# adcUart.net
KiCad netlist of a schematic drawn in EAGLE
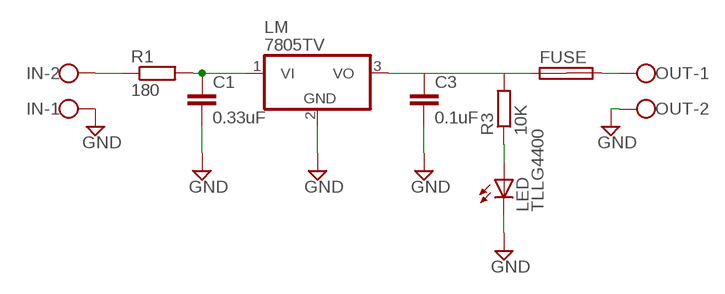
[diagram p0: schematic, sheet 1]

(export (version "E")
  (design (tool "Eeschema 10.0.6"))
  (components
    (comp (ref "C1")
      (value "0.33uF")
      (footprint "eagle-import:C025-024X044")
      (libsource (lib "eagle-import") (part "C-EU025-024X044"))
    )
    (comp (ref "C3")
      (value "0.1uF")
      (footprint "eagle-import:C025-024X044")
      (libsource (lib "eagle-import") (part "C-EU025-024X044"))
    )
    (comp (ref "FUSE")
      (value "SHK20L")
      (footprint "eagle-import:SHK20L")
      (libsource (lib "eagle-import") (part "SHK20L"))
    )
    (comp (ref "IN")
      (value "W237-102")
      (footprint "eagle-import:W237-102")
      (fields (field (name "MPN") "237-102"))
      (libsource (lib "eagle-import") (part "W237-102"))
    )
    (comp (ref "LED")
      (value "TLLG4400")
      (footprint "eagle-import:LED3MM")
      (fields (field (name "MF") "VISHAY SEMICONDUCTOR"))
      (libsource (lib "eagle-import") (part "TLLG4400"))
    )
    (comp (ref "LM")
      (value "7805TV")
      (footprint "eagle-import:TO220V")
      (libsource (lib "eagle-import") (part "78TV05"))
    )
    (comp (ref "OUT")
      (value "W237-102")
      (footprint "eagle-import:W237-102")
      (fields (field (name "MPN") "237-102"))
      (libsource (lib "eagle-import") (part "W237-102"))
    )
    (comp (ref "R1")
      (value "180")
      (footprint "eagle-import:0617_22")
      (libsource (lib "eagle-import") (part "resistor_R-EU_0617/22"))
    )
    (comp (ref "R3")
      (value "10K")
      (footprint "eagle-import:0204_7")
      (libsource (lib "eagle-import") (part "R-EU_0204/7"))
    )
  )
  (nets
    (net (code "1") (name "GND") (class "Default")
      (node (ref "C1") (pin "2") (pinfunction "2_2") (pintype "passive"))
      (node (ref "C3") (pin "2") (pinfunction "2_2") (pintype "passive"))
      (node (ref "IN") (pin "1") (pinfunction "KL_1") (pintype "passive"))
      (node (ref "LED") (pin "K") (pinfunction "C_K") (pintype "passive"))
      (node (ref "LM") (pin "2") (pinfunction "GND_2") (pintype "passive"))
      (node (ref "OUT") (pin "2") (pinfunction "KL_2") (pintype "passive"))
    )
    (net (code "2") (name "Net-(INB-KL)") (class "Default")
      (node (ref "IN") (pin "2") (pinfunction "KL_2") (pintype "passive"))
      (node (ref "R1") (pin "1") (pinfunction "1_1") (pintype "passive"))
    )
    (net (code "3") (name "Net-(LED-PadA)") (class "Default")
      (node (ref "LED") (pin "A") (pinfunction "A_A") (pintype "passive"))
      (node (ref "R3") (pin "1") (pinfunction "1_1") (pintype "passive"))
    )
    (net (code "4") (name "Net-(LM-VI)") (class "Default")
      (node (ref "C1") (pin "1") (pinfunction "1_1") (pintype "passive"))
      (node (ref "LM") (pin "1") (pinfunction "VI_1") (pintype "input"))
      (node (ref "R1") (pin "2") (pinfunction "2_2") (pintype "passive"))
    )
    (net (code "5") (name "Net-(LM-VO)") (class "Default")
      (node (ref "C3") (pin "1") (pinfunction "1_1") (pintype "passive"))
      (node (ref "FUSE") (pin "1A") (pinfunction "1A_1A") (pintype "passive"))
      (node (ref "LM") (pin "3") (pinfunction "VO_3") (pintype "passive"))
      (node (ref "R3") (pin "2") (pinfunction "2_2") (pintype "passive"))
    )
    (net (code "6") (name "Net-(OUTA-KL)") (class "Default")
      (node (ref "FUSE") (pin "2A") (pinfunction "2A_2A") (pintype "passive"))
      (node (ref "OUT") (pin "1") (pinfunction "KL_1") (pintype "passive"))
    )
    (net (code "7") (name "unconnected-(FUSE-Pad1B)") (class "Default")
      (node (ref "FUSE") (pin "1B") (pinfunction "1B_1B") (pintype "passive"))
    )
    (net (code "8") (name "unconnected-(FUSE-Pad2B)") (class "Default")
      (node (ref "FUSE") (pin "2B") (pinfunction "2B_2B") (pintype "passive"))
    )
  )
)
